# PoEpi_v3.net
KiCad netlist of a schematic drawn in EAGLE
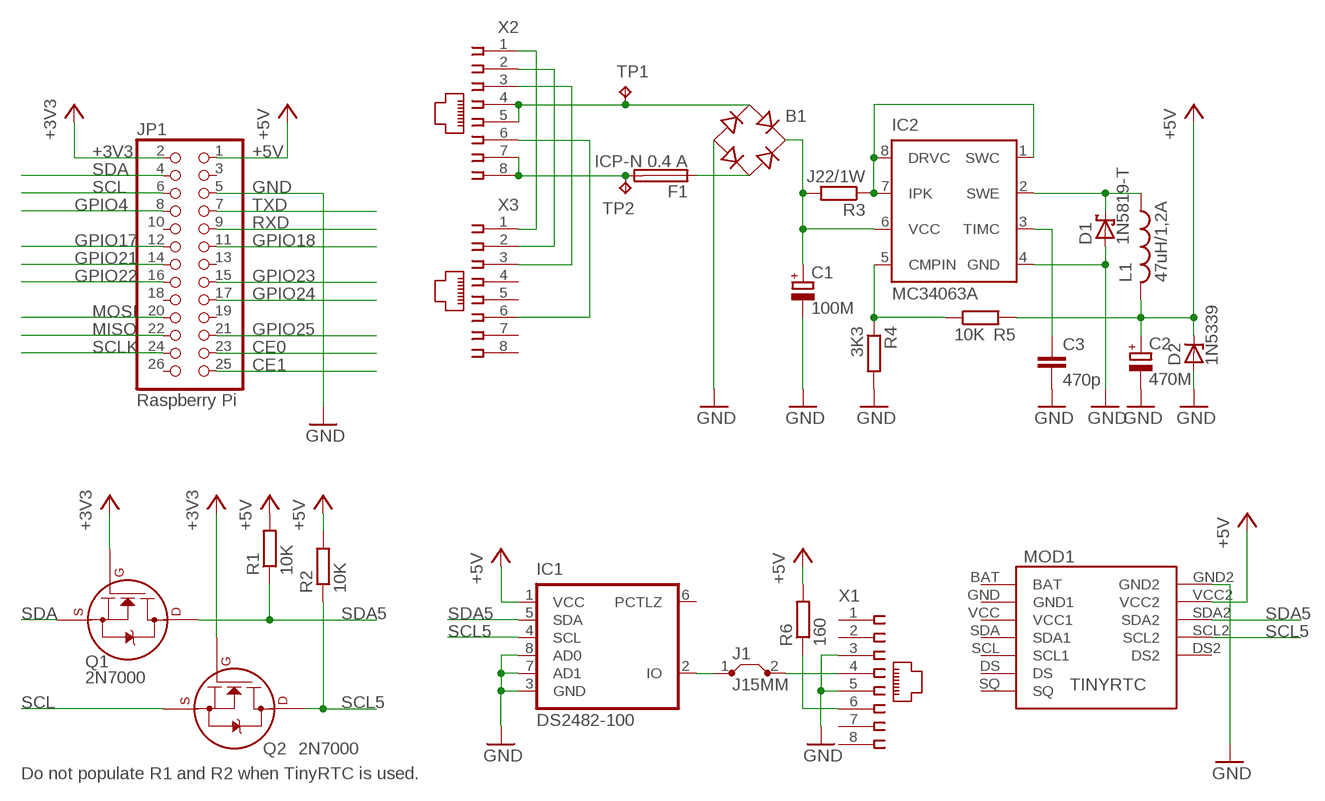
[diagram p0: schematic, sheet 1]

(export (version "E")
  (design (tool "Eeschema 10.0.6"))
  (components
    (comp (ref "B1")
      (value "B-DIL")
      (footprint "eagle-import:B-DIL")
      (libsource (lib "eagle-import") (part "B-DIL"))
    )
    (comp (ref "C1")
      (value "100M")
      (footprint "eagle-import:E3,5-8")
      (libsource (lib "eagle-import") (part "CPOL-EUE3.5-8"))
    )
    (comp (ref "C2")
      (value "470M")
      (footprint "eagle-import:E3,5-8")
      (libsource (lib "eagle-import") (part "CPOL-EUE3.5-8"))
    )
    (comp (ref "C3")
      (value "470p")
      (footprint "eagle-import:C050-024X044")
      (libsource (lib "eagle-import") (part "C-EU050-024X044"))
    )
    (comp (ref "D1")
      (value "1N5819-T")
      (footprint "eagle-import:DO41-7.6")
      (libsource (lib "eagle-import") (part "1N5819-T"))
    )
    (comp (ref "D2")
      (value "1N5339")
      (footprint "eagle-import:C1702-15")
      (libsource (lib "eagle-import") (part "1N5333"))
    )
    (comp (ref "F1")
      (value "ICP-N 0.4 A")
      (footprint "eagle-import:TO92-2")
      (libsource (lib "eagle-import") (part "FUSETO92-2"))
    )
    (comp (ref "IC1")
      (value "DS2482-100")
      (footprint "eagle-import:SO08")
      (libsource (lib "eagle-import") (part "DS2482-100"))
    )
    (comp (ref "IC2")
      (value "MC34063A")
      (footprint "eagle-import:DIL8")
      (libsource (lib "eagle-import") (part "MC34063A"))
    )
    (comp (ref "J1")
      (value "J15MM")
      (footprint "eagle-import:15")
      (libsource (lib "eagle-import") (part "J15MM"))
    )
    (comp (ref "JP1")
      (value "Raspberry Pi")
      (footprint "eagle-import:2X13")
      (libsource (lib "eagle-import") (part "PINHD-2X13INV"))
    )
    (comp (ref "L1")
      (value "47uH/1,2A")
      (footprint "eagle-import:6000-XXXX-RC")
      (libsource (lib "eagle-import") (part "L-US6000-XXX-RC"))
    )
    (comp (ref "MOD1")
      (value "TINYRTC")
      (footprint "eagle-import:TINYRTCMODULE")
      (libsource (lib "eagle-import") (part "TINYRTC"))
    )
    (comp (ref "Q1")
      (value "2N7000")
      (footprint "eagle-import:TO92-")
      (libsource (lib "eagle-import") (part "2N700_TO92-"))
    )
    (comp (ref "Q2")
      (value "2N7000")
      (footprint "eagle-import:TO92-")
      (libsource (lib "eagle-import") (part "2N700_TO92-"))
    )
    (comp (ref "R1")
      (value "10K")
      (footprint "eagle-import:0204_7")
      (libsource (lib "eagle-import") (part "R-EU_0204/7"))
    )
    (comp (ref "R2")
      (value "10K")
      (footprint "eagle-import:0204_7")
      (libsource (lib "eagle-import") (part "R-EU_0204/7"))
    )
    (comp (ref "R3")
      (value "J22/1W")
      (footprint "eagle-import:0617_17")
      (libsource (lib "eagle-import") (part "R-EU_0617/17"))
    )
    (comp (ref "R4")
      (value "3K3")
      (footprint "eagle-import:0204_7")
      (libsource (lib "eagle-import") (part "R-EU_0204/7"))
    )
    (comp (ref "R5")
      (value "10K")
      (footprint "eagle-import:0204_7")
      (libsource (lib "eagle-import") (part "R-EU_0204/7"))
    )
    (comp (ref "R6")
      (value "160")
      (footprint "eagle-import:0204_7")
      (libsource (lib "eagle-import") (part "R-EU_0204/7"))
    )
    (comp (ref "TP1")
      (value "TPPAD1-13Y")
      (footprint "eagle-import:P1-13Y")
      (libsource (lib "eagle-import") (part "TPPAD1-13Y"))
    )
    (comp (ref "TP2")
      (value "TPPAD1-13Y")
      (footprint "eagle-import:P1-13Y")
      (libsource (lib "eagle-import") (part "TPPAD1-13Y"))
    )
    (comp (ref "X1")
      (value "520251-4")
      (footprint "eagle-import:520251-4")
      (libsource (lib "eagle-import") (part "520251-4"))
    )
    (comp (ref "X2")
      (value "520251-4")
      (footprint "eagle-import:520251-4")
      (libsource (lib "eagle-import") (part "520251-4"))
    )
    (comp (ref "X3")
      (value "520251-4")
      (footprint "eagle-import:520251-4")
      (libsource (lib "eagle-import") (part "520251-4"))
    )
  )
  (nets
    (net (code "1") (name "+3V3") (class "Default")
      (node (ref "JP1") (pin "2") (pinfunction "1_2") (pintype "passive"))
      (node (ref "Q1") (pin "2") (pinfunction "G_2") (pintype "tri_state"))
      (node (ref "Q2") (pin "2") (pinfunction "G_2") (pintype "tri_state"))
    )
    (net (code "2") (name "+5V") (class "Default")
      (node (ref "C2") (pin "+") (pinfunction "+_+") (pintype "passive"))
      (node (ref "D2") (pin "C") (pinfunction "C_C") (pintype "passive"))
      (node (ref "IC1") (pin "1") (pinfunction "VCC_1") (pintype "power_in"))
      (node (ref "JP1") (pin "1") (pinfunction "2_1") (pintype "passive"))
      (node (ref "L1") (pin "2") (pinfunction "2_2") (pintype "passive"))
      (node (ref "MOD1") (pin "VCC2") (pinfunction "VCC2_VCC2") (pintype "power_in"))
      (node (ref "R1") (pin "2") (pinfunction "2_2") (pintype "passive"))
      (node (ref "R2") (pin "2") (pinfunction "2_2") (pintype "passive"))
      (node (ref "R5") (pin "2") (pinfunction "2_2") (pintype "passive"))
      (node (ref "R6") (pin "2") (pinfunction "2_2") (pintype "passive"))
    )
    (net (code "3") (name "/BAT") (class "Default")
      (node (ref "MOD1") (pin "BAT") (pinfunction "BAT_BAT") (pintype "power_in"))
    )
    (net (code "4") (name "/CE0") (class "Default")
      (node (ref "JP1") (pin "23") (pinfunction "24_23") (pintype "passive"))
    )
    (net (code "5") (name "/CE1") (class "Default")
      (node (ref "JP1") (pin "25") (pinfunction "26_25") (pintype "passive"))
    )
    (net (code "6") (name "/GND1") (class "Default")
      (node (ref "MOD1") (pin "GND") (pinfunction "GND1_GND") (pintype "power_in"))
    )
    (net (code "7") (name "/GPIO4") (class "Default")
      (node (ref "JP1") (pin "8") (pinfunction "7_8") (pintype "passive"))
    )
    (net (code "8") (name "/GPIO17") (class "Default")
      (node (ref "JP1") (pin "12") (pinfunction "11_12") (pintype "passive"))
    )
    (net (code "9") (name "/GPIO18") (class "Default")
      (node (ref "JP1") (pin "11") (pinfunction "12_11") (pintype "passive"))
    )
    (net (code "10") (name "/GPIO21") (class "Default")
      (node (ref "JP1") (pin "14") (pinfunction "13_14") (pintype "passive"))
    )
    (net (code "11") (name "/GPIO22") (class "Default")
      (node (ref "JP1") (pin "16") (pinfunction "15_16") (pintype "passive"))
    )
    (net (code "12") (name "/GPIO23") (class "Default")
      (node (ref "JP1") (pin "15") (pinfunction "16_15") (pintype "passive"))
    )
    (net (code "13") (name "/GPIO24") (class "Default")
      (node (ref "JP1") (pin "17") (pinfunction "18_17") (pintype "passive"))
    )
    (net (code "14") (name "/GPIO25") (class "Default")
      (node (ref "JP1") (pin "21") (pinfunction "22_21") (pintype "passive"))
    )
    (net (code "15") (name "/MISO") (class "Default")
      (node (ref "JP1") (pin "22") (pinfunction "21_22") (pintype "passive"))
    )
    (net (code "16") (name "/MOSI") (class "Default")
      (node (ref "JP1") (pin "20") (pinfunction "19_20") (pintype "passive"))
    )
    (net (code "17") (name "/RXD") (class "Default")
      (node (ref "JP1") (pin "9") (pinfunction "10_9") (pintype "passive"))
    )
    (net (code "18") (name "/SCL") (class "Default")
      (node (ref "JP1") (pin "6") (pinfunction "5_6") (pintype "passive"))
      (node (ref "Q2") (pin "3") (pinfunction "S_3") (pintype "bidirectional"))
    )
    (net (code "19") (name "/SCL5") (class "Default")
      (node (ref "IC1") (pin "4") (pinfunction "SCL_4") (pintype "input"))
      (node (ref "MOD1") (pin "SCL2") (pinfunction "SCL2_SCL2") (pintype "input"))
      (node (ref "Q2") (pin "1") (pinfunction "D_1") (pintype "bidirectional"))
      (node (ref "R2") (pin "1") (pinfunction "1_1") (pintype "passive"))
    )
    (net (code "20") (name "/SCLK") (class "Default")
      (node (ref "JP1") (pin "24") (pinfunction "23_24") (pintype "passive"))
    )
    (net (code "21") (name "/SDA") (class "Default")
      (node (ref "JP1") (pin "4") (pinfunction "3_4") (pintype "passive"))
      (node (ref "Q1") (pin "3") (pinfunction "S_3") (pintype "bidirectional"))
    )
    (net (code "22") (name "/SDA5") (class "Default")
      (node (ref "IC1") (pin "5") (pinfunction "SDA_5") (pintype "input"))
      (node (ref "MOD1") (pin "SDA2") (pinfunction "SDA2_SDA2") (pintype "bidirectional"))
      (node (ref "Q1") (pin "1") (pinfunction "D_1") (pintype "bidirectional"))
      (node (ref "R1") (pin "1") (pinfunction "1_1") (pintype "passive"))
    )
    (net (code "23") (name "/TXD") (class "Default")
      (node (ref "JP1") (pin "7") (pinfunction "8_7") (pintype "passive"))
    )
    (net (code "24") (name "/VCC1") (class "Default")
      (node (ref "MOD1") (pin "VCC") (pinfunction "VCC1_VCC") (pintype "power_in"))
    )
    (net (code "25") (name "GND") (class "Default")
      (node (ref "B1") (pin "-") (pinfunction "-_-") (pintype "passive"))
      (node (ref "C1") (pin "-") (pinfunction "-_-") (pintype "passive"))
      (node (ref "C2") (pin "-") (pinfunction "-_-") (pintype "passive"))
      (node (ref "C3") (pin "2") (pinfunction "2_2") (pintype "passive"))
      (node (ref "D1") (pin "A") (pinfunction "A_A") (pintype "passive"))
      (node (ref "D2") (pin "A") (pinfunction "A_A") (pintype "passive"))
      (node (ref "IC1") (pin "3") (pinfunction "GND_3") (pintype "power_in"))
      (node (ref "IC1") (pin "7") (pinfunction "AD1_7") (pintype "bidirectional"))
      (node (ref "IC1") (pin "8") (pinfunction "AD0_8") (pintype "bidirectional"))
      (node (ref "IC2") (pin "4") (pinfunction "GND_4") (pintype "power_in"))
      (node (ref "JP1") (pin "5") (pinfunction "6_5") (pintype "passive"))
      (node (ref "MOD1") (pin "GND2") (pinfunction "GND2_GND2") (pintype "power_in"))
      (node (ref "R4") (pin "2") (pinfunction "2_2") (pintype "passive"))
      (node (ref "X1") (pin "3") (pinfunction "3_3") (pintype "passive"))
      (node (ref "X1") (pin "5") (pinfunction "5_5") (pintype "passive"))
    )
    (net (code "26") (name "Net-(B1-PadAC1)") (class "Default")
      (node (ref "B1") (pin "AC1") (pinfunction "AC1_AC1") (pintype "passive"))
      (node (ref "TP1") (pin "TP") (pinfunction "TP_TP") (pintype "input"))
      (node (ref "X2") (pin "4") (pinfunction "4_4") (pintype "passive"))
      (node (ref "X2") (pin "5") (pinfunction "5_5") (pintype "passive"))
    )
    (net (code "27") (name "Net-(B1-PadAC2)") (class "Default")
      (node (ref "B1") (pin "AC2") (pinfunction "AC2_AC2") (pintype "passive"))
      (node (ref "F1") (pin "1") (pinfunction "1_1") (pintype "passive"))
    )
    (net (code "28") (name "Net-(F1-2)") (class "Default")
      (node (ref "F1") (pin "3") (pinfunction "2_3") (pintype "passive"))
      (node (ref "TP2") (pin "TP") (pinfunction "TP_TP") (pintype "input"))
      (node (ref "X2") (pin "7") (pinfunction "7_7") (pintype "passive"))
      (node (ref "X2") (pin "8") (pinfunction "8_8") (pintype "passive"))
    )
    (net (code "29") (name "Net-(IC1-IO)") (class "Default")
      (node (ref "IC1") (pin "2") (pinfunction "IO_2") (pintype "bidirectional"))
      (node (ref "J1") (pin "1") (pinfunction "1_1") (pintype "passive"))
    )
    (net (code "30") (name "Net-(IC2-CMPIN)") (class "Default")
      (node (ref "IC2") (pin "5") (pinfunction "CMPIN_5") (pintype "input"))
      (node (ref "R4") (pin "1") (pinfunction "1_1") (pintype "passive"))
      (node (ref "R5") (pin "1") (pinfunction "1_1") (pintype "passive"))
    )
    (net (code "31") (name "Net-(IC2-DRVC)") (class "Default")
      (node (ref "IC2") (pin "1") (pinfunction "SWC_1") (pintype "open_collector"))
      (node (ref "IC2") (pin "7") (pinfunction "IPK_7") (pintype "input"))
      (node (ref "IC2") (pin "8") (pinfunction "DRVC_8") (pintype "input"))
      (node (ref "R3") (pin "1") (pinfunction "1_1") (pintype "passive"))
    )
    (net (code "32") (name "Net-(IC2-SWE)") (class "Default")
      (node (ref "D1") (pin "C") (pinfunction "C_C") (pintype "passive"))
      (node (ref "IC2") (pin "2") (pinfunction "SWE_2") (pintype "output"))
      (node (ref "L1") (pin "1") (pinfunction "1_1") (pintype "passive"))
    )
    (net (code "33") (name "Net-(IC2-TIMC)") (class "Default")
      (node (ref "C3") (pin "1") (pinfunction "1_1") (pintype "passive"))
      (node (ref "IC2") (pin "3") (pinfunction "TIMC_3") (pintype "output"))
    )
    (net (code "34") (name "Net-(IC2-VCC)") (class "Default")
      (node (ref "B1") (pin "+") (pinfunction "+_+") (pintype "passive"))
      (node (ref "C1") (pin "+") (pinfunction "+_+") (pintype "passive"))
      (node (ref "IC2") (pin "6") (pinfunction "VCC_6") (pintype "power_in"))
      (node (ref "R3") (pin "2") (pinfunction "2_2") (pintype "passive"))
    )
    (net (code "35") (name "Net-(J1-Pad2)") (class "Default")
      (node (ref "J1") (pin "2") (pinfunction "2_2") (pintype "passive"))
      (node (ref "X1") (pin "4") (pinfunction "4_4") (pintype "passive"))
    )
    (net (code "36") (name "Net-(R6-Pad1)") (class "Default")
      (node (ref "R6") (pin "1") (pinfunction "1_1") (pintype "passive"))
      (node (ref "X1") (pin "6") (pinfunction "6_6") (pintype "passive"))
    )
    (net (code "37") (name "Net-(X2-Pad1)") (class "Default")
      (node (ref "X2") (pin "1") (pinfunction "1_1") (pintype "passive"))
      (node (ref "X3") (pin "1") (pinfunction "1_1") (pintype "passive"))
    )
    (net (code "38") (name "Net-(X2-Pad2)") (class "Default")
      (node (ref "X2") (pin "2") (pinfunction "2_2") (pintype "passive"))
      (node (ref "X3") (pin "2") (pinfunction "2_2") (pintype "passive"))
    )
    (net (code "39") (name "Net-(X2-Pad3)") (class "Default")
      (node (ref "X2") (pin "3") (pinfunction "3_3") (pintype "passive"))
      (node (ref "X3") (pin "3") (pinfunction "3_3") (pintype "passive"))
    )
    (net (code "40") (name "Net-(X2-Pad6)") (class "Default")
      (node (ref "X2") (pin "6") (pinfunction "6_6") (pintype "passive"))
      (node (ref "X3") (pin "6") (pinfunction "6_6") (pintype "passive"))
    )
    (net (code "41") (name "unconnected-(IC1-PCTLZ-Pad6)") (class "Default")
      (node (ref "IC1") (pin "6") (pinfunction "PCTLZ_6") (pintype "output"))
    )
    (net (code "42") (name "unconnected-(JP1-4-Pad3)") (class "Default")
      (node (ref "JP1") (pin "3") (pinfunction "4_3") (pintype "passive"))
    )
    (net (code "43") (name "unconnected-(JP1-9-Pad10)") (class "Default")
      (node (ref "JP1") (pin "10") (pinfunction "9_10") (pintype "passive"))
    )
    (net (code "44") (name "unconnected-(JP1-14-Pad13)") (class "Default")
      (node (ref "JP1") (pin "13") (pinfunction "14_13") (pintype "passive"))
    )
    (net (code "45") (name "unconnected-(JP1-17-Pad18)") (class "Default")
      (node (ref "JP1") (pin "18") (pinfunction "17_18") (pintype "passive"))
    )
    (net (code "46") (name "unconnected-(JP1-20-Pad19)") (class "Default")
      (node (ref "JP1") (pin "19") (pinfunction "20_19") (pintype "passive"))
    )
    (net (code "47") (name "unconnected-(JP1-25-Pad26)") (class "Default")
      (node (ref "JP1") (pin "26") (pinfunction "25_26") (pintype "passive"))
    )
    (net (code "48") (name "unconnected-(MOD1-PadDS)") (class "Default")
      (node (ref "MOD1") (pin "DS") (pinfunction "DS_DS") (pintype "bidirectional"))
    )
    (net (code "49") (name "unconnected-(MOD1-PadDS2)") (class "Default")
      (node (ref "MOD1") (pin "DS2") (pinfunction "DS2_DS2") (pintype "bidirectional"))
    )
    (net (code "50") (name "unconnected-(MOD1-PadSQ)") (class "Default")
      (node (ref "MOD1") (pin "SQ") (pinfunction "SQ_SQ") (pintype "output"))
    )
    (net (code "51") (name "unconnected-(MOD1-SCL1-PadSCL)") (class "Default")
      (node (ref "MOD1") (pin "SCL") (pinfunction "SCL1_SCL") (pintype "input"))
    )
    (net (code "52") (name "unconnected-(MOD1-SDA1-PadSDA)") (class "Default")
      (node (ref "MOD1") (pin "SDA") (pinfunction "SDA1_SDA") (pintype "bidirectional"))
    )
    (net (code "53") (name "unconnected-(X1-Pad1)") (class "Default")
      (node (ref "X1") (pin "1") (pinfunction "1_1") (pintype "passive"))
    )
    (net (code "54") (name "unconnected-(X1-Pad2)") (class "Default")
      (node (ref "X1") (pin "2") (pinfunction "2_2") (pintype "passive"))
    )
    (net (code "55") (name "unconnected-(X1-Pad7)") (class "Default")
      (node (ref "X1") (pin "7") (pinfunction "7_7") (pintype "passive"))
    )
    (net (code "56") (name "unconnected-(X1-Pad8)") (class "Default")
      (node (ref "X1") (pin "8") (pinfunction "8_8") (pintype "passive"))
    )
    (net (code "57") (name "unconnected-(X3-Pad4)") (class "Default")
      (node (ref "X3") (pin "4") (pinfunction "4_4") (pintype "passive"))
    )
    (net (code "58") (name "unconnected-(X3-Pad5)") (class "Default")
      (node (ref "X3") (pin "5") (pinfunction "5_5") (pintype "passive"))
    )
    (net (code "59") (name "unconnected-(X3-Pad7)") (class "Default")
      (node (ref "X3") (pin "7") (pinfunction "7_7") (pintype "passive"))
    )
    (net (code "60") (name "unconnected-(X3-Pad8)") (class "Default")
      (node (ref "X3") (pin "8") (pinfunction "8_8") (pintype "passive"))
    )
  )
)
